# uart_usb_bridge.net
KiCad netlist of a schematic drawn in Altium Designer
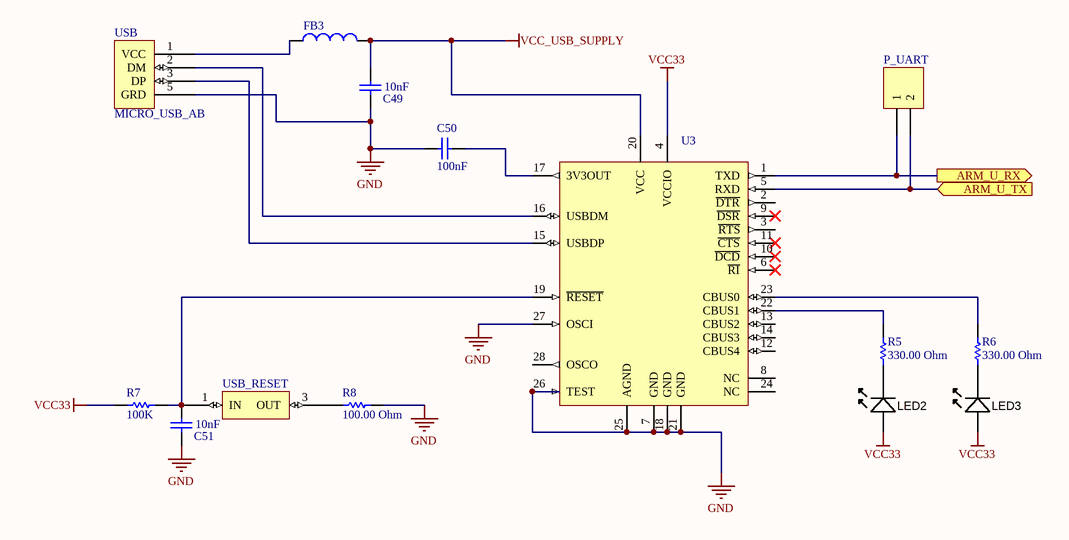
[diagram p0: uart_usb_bridge.SchDoc]

(export (version "E")
  (design (tool "Eeschema 10.0.6"))
  (components
    (comp (ref "C49")
      (value "10nF")
      (footprint "CAPC0805(2012)75_N")
      (description "CAP 10nF 50V ±10% 0805 (2012 Metric) Thickness 0.75mm SMD")
      (fields (field (name "TOLERANCE") "±10%"))
      (libsource (lib "Altium Content Vault") (part "CMP-1036-03842-1"))
    )
    (comp (ref "C50")
      (value "100nF")
      (footprint "CAPC0805(2012)100_M")
      (description "CAP 100nF 50V ±10% 0805 (2012 Metric) Thickness 1mm SMD")
      (fields (field (name "TOLERANCE") "±10%"))
      (libsource (lib "Altium Content Vault") (part "CMP-1036-04420-1"))
    )
    (comp (ref "C51")
      (value "10nF")
      (footprint "CAPC0805(2012)75_N")
      (description "CAP 10nF 50V ±10% 0805 (2012 Metric) Thickness 0.75mm SMD")
      (fields (field (name "TOLERANCE") "±10%"))
      (libsource (lib "Altium Content Vault") (part "CMP-1036-03842-1"))
    )
    (comp (ref "FB3")
      (value "Inductor")
      (footprint "INDC3216")
      (fields (field (name "PUBLISHER") "Altium Limited"))
      (libsource (lib "Miscellaneous Devices") (part "Inductor"))
    )
    (comp (ref "LED2")
      (value "Red")
      (footprint "LED-0805-A")
      (description "LED, 0805 SMD, Red")
      (libsource (lib "PBL - Light Sources") (part "LED_SMD_Red_0805"))
    )
    (comp (ref "LED3")
      (value "Red")
      (footprint "LED-0805-A")
      (description "LED, 0805 SMD, Red")
      (libsource (lib "PBL - Light Sources") (part "LED_SMD_Red_0805"))
    )
    (comp (ref "P_UART")
      (value "Header 2")
      (footprint "HDR1X2")
      (description "Header, 2-Pin")
      (fields (field (name "PUBLISHER") "Altium Limited"))
      (libsource (lib "Miscellaneous Connectors") (part "Header 2"))
    )
    (comp (ref "R5")
      (value "330.00 Ohm")
      (footprint "RESC0805(2012)_M")
      (description "330R 0.125W 1% 0805 (2012 Metric)  SMD")
      (fields (field (name "POWER") "0.125 W") (field (name "TOLERANCE") "1 %"))
      (libsource (lib "Altium Content Vault") (part "CMP-1013-00454-1"))
    )
    (comp (ref "R6")
      (value "330.00 Ohm")
      (footprint "RESC0805(2012)_M")
      (description "330R 0.125W 1% 0805 (2012 Metric)  SMD")
      (fields (field (name "POWER") "0.125 W") (field (name "TOLERANCE") "1 %"))
      (libsource (lib "Altium Content Vault") (part "CMP-1013-00454-1"))
    )
    (comp (ref "R7")
      (value "100K")
      (footprint "RESC0805(2012)_L")
      (description "100K 0.125W 5% 0805 (2012 Metric)  SMD")
      (fields (field (name "TOLERANCE") "5 %") (field (name "POWER") "0.125 W"))
      (libsource (lib "Altium Content Vault") (part "CMP-1013-00122-1"))
    )
    (comp (ref "R8")
      (value "100.00 Ohm")
      (footprint "RESC0805(2012)_M")
      (description "100R 0.125W 5% 0805 (2012 Metric)  SMD")
      (fields (field (name "TOLERANCE") "5 %") (field (name "POWER") "0.125 W"))
      (libsource (lib "Altium Content Vault") (part "CMP-1013-00050-1"))
    )
    (comp (ref "U3")
      (value "FT232RL-Reel")
      (footprint "SSOP-28_N")
      (description "USB UART Asynchronous Serial Data Transfer Chip, SSOP-28, Tape and Reel")
      (libsource (lib "FTDI Communication") (part "FT232RL-Reel"))
    )
    (comp (ref "USB")
      (value "MICRO_USB_AB")
      (footprint "MICRO_USB_AB")
      (libsource (lib "MICROUSB") (part "MICRO_USB_AB"))
    )
    (comp (ref "USB_RESET")
      (value "BUTTON")
      (footprint "BUTTON")
      (libsource (lib "PowerConnector") (part "BUTTON"))
    )
  )
  (nets
    (net (code "1") (name "/ARM_U_RX") (class "Default")
      (node (ref "P_UART") (pin "1") (pinfunction "1_1") (pintype "passive"))
      (node (ref "U3") (pin "1") (pinfunction "TXD_1") (pintype "output"))
    )
    (net (code "2") (name "/ARM_U_TX") (class "Default")
      (node (ref "P_UART") (pin "2") (pinfunction "2_2") (pintype "passive"))
      (node (ref "U3") (pin "5") (pinfunction "RXD_5") (pintype "input"))
    )
    (net (code "3") (name "GND") (class "Default")
      (node (ref "C49") (pin "1") (pinfunction "1_1") (pintype "passive"))
      (node (ref "C50") (pin "2") (pinfunction "2_2") (pintype "passive"))
      (node (ref "C51") (pin "1") (pinfunction "1_1") (pintype "passive"))
      (node (ref "R8") (pin "2") (pinfunction "2_2") (pintype "passive"))
      (node (ref "U3") (pin "18") (pinfunction "GND_18") (pintype "power_in"))
      (node (ref "U3") (pin "21") (pinfunction "GND_21") (pintype "power_in"))
      (node (ref "U3") (pin "25") (pinfunction "AGND_25") (pintype "power_in"))
      (node (ref "U3") (pin "26") (pinfunction "TEST_26") (pintype "input"))
      (node (ref "U3") (pin "27") (pinfunction "OSCI_27") (pintype "input"))
      (node (ref "U3") (pin "7") (pinfunction "GND_7") (pintype "power_in"))
      (node (ref "USB") (pin "5") (pinfunction "GRD_5") (pintype "power_in"))
    )
    (net (code "4") (name "Net-(LED2-PadK)") (class "Default")
      (node (ref "LED2") (pin "K") (pinfunction "K_K") (pintype "passive"))
      (node (ref "R5") (pin "1") (pinfunction "1_1") (pintype "passive"))
    )
    (net (code "5") (name "Net-(LED3-PadK)") (class "Default")
      (node (ref "LED3") (pin "K") (pinfunction "K_K") (pintype "passive"))
      (node (ref "R6") (pin "1") (pinfunction "1_1") (pintype "passive"))
    )
    (net (code "6") (name "Net-(U3-3V3OUT)") (class "Default")
      (node (ref "C50") (pin "1") (pinfunction "1_1") (pintype "passive"))
      (node (ref "U3") (pin "17") (pinfunction "3V3OUT_17") (pintype "output"))
    )
    (net (code "7") (name "Net-(U3-CBUS0)") (class "Default")
      (node (ref "R6") (pin "2") (pinfunction "2_2") (pintype "passive"))
      (node (ref "U3") (pin "23") (pinfunction "CBUS0_23") (pintype "bidirectional"))
    )
    (net (code "8") (name "Net-(U3-CBUS1)") (class "Default")
      (node (ref "R5") (pin "2") (pinfunction "2_2") (pintype "passive"))
      (node (ref "U3") (pin "22") (pinfunction "CBUS1_22") (pintype "bidirectional"))
    )
    (net (code "9") (name "Net-(U3-USBDM)") (class "Default")
      (node (ref "U3") (pin "16") (pinfunction "USBDM_16") (pintype "bidirectional"))
      (node (ref "USB") (pin "2") (pinfunction "DM_2") (pintype "bidirectional"))
    )
    (net (code "10") (name "Net-(U3-USBDP)") (class "Default")
      (node (ref "U3") (pin "15") (pinfunction "USBDP_15") (pintype "bidirectional"))
      (node (ref "USB") (pin "3") (pinfunction "DP_3") (pintype "bidirectional"))
    )
    (net (code "11") (name "Net-(U3-~{RESET})") (class "Default")
      (node (ref "C51") (pin "2") (pinfunction "2_2") (pintype "passive"))
      (node (ref "R7") (pin "1") (pinfunction "1_1") (pintype "passive"))
      (node (ref "U3") (pin "19") (pinfunction "~{RESET}_19") (pintype "input"))
      (node (ref "USB_RESET") (pin "1") (pinfunction "IN_1") (pintype "bidirectional"))
    )
    (net (code "12") (name "Net-(USB-VCC)") (class "Default")
      (node (ref "FB3") (pin "1") (pinfunction "1_1") (pintype "passive"))
      (node (ref "USB") (pin "1") (pinfunction "VCC_1") (pintype "power_in"))
    )
    (net (code "13") (name "Net-(USB_RESET-OUT)") (class "Default")
      (node (ref "R8") (pin "1") (pinfunction "1_1") (pintype "passive"))
      (node (ref "USB_RESET") (pin "3") (pinfunction "OUT_3") (pintype "bidirectional"))
    )
    (net (code "14") (name "VCC33") (class "Default")
      (node (ref "LED2") (pin "A") (pinfunction "A_A") (pintype "passive"))
      (node (ref "LED3") (pin "A") (pinfunction "A_A") (pintype "passive"))
      (node (ref "R7") (pin "2") (pinfunction "2_2") (pintype "passive"))
      (node (ref "U3") (pin "4") (pinfunction "VCCIO_4") (pintype "power_in"))
    )
    (net (code "15") (name "VCC_USB_SUPPLY") (class "Default")
      (node (ref "C49") (pin "2") (pinfunction "2_2") (pintype "passive"))
      (node (ref "FB3") (pin "2") (pinfunction "2_2") (pintype "passive"))
      (node (ref "U3") (pin "20") (pinfunction "VCC_20") (pintype "power_in"))
    )
    (net (code "16") (name "unconnected-(U3-CBUS2-Pad13)") (class "Default")
      (node (ref "U3") (pin "13") (pinfunction "CBUS2_13") (pintype "bidirectional"))
    )
    (net (code "17") (name "unconnected-(U3-CBUS3-Pad14)") (class "Default")
      (node (ref "U3") (pin "14") (pinfunction "CBUS3_14") (pintype "bidirectional"))
    )
    (net (code "18") (name "unconnected-(U3-CBUS4-Pad12)") (class "Default")
      (node (ref "U3") (pin "12") (pinfunction "CBUS4_12") (pintype "bidirectional"))
    )
    (net (code "19") (name "unconnected-(U3-NC-Pad8)") (class "Default")
      (node (ref "U3") (pin "8") (pinfunction "NC_8") (pintype "passive"))
    )
    (net (code "20") (name "unconnected-(U3-NC-Pad24)") (class "Default")
      (node (ref "U3") (pin "24") (pinfunction "NC_24") (pintype "passive"))
    )
    (net (code "21") (name "unconnected-(U3-OSCO-Pad28)") (class "Default")
      (node (ref "U3") (pin "28") (pinfunction "OSCO_28") (pintype "output"))
    )
    (net (code "22") (name "unconnected-(U3-~{CTS}-Pad11)") (class "Default")
      (node (ref "U3") (pin "11") (pinfunction "~{CTS}_11") (pintype "input+no_connect"))
    )
    (net (code "23") (name "unconnected-(U3-~{DCD}-Pad10)") (class "Default")
      (node (ref "U3") (pin "10") (pinfunction "~{DCD}_10") (pintype "input+no_connect"))
    )
    (net (code "24") (name "unconnected-(U3-~{DSR}-Pad9)") (class "Default")
      (node (ref "U3") (pin "9") (pinfunction "~{DSR}_9") (pintype "input+no_connect"))
    )
    (net (code "25") (name "unconnected-(U3-~{DTR}-Pad2)") (class "Default")
      (node (ref "U3") (pin "2") (pinfunction "~{DTR}_2") (pintype "output"))
    )
    (net (code "26") (name "unconnected-(U3-~{RI}-Pad6)") (class "Default")
      (node (ref "U3") (pin "6") (pinfunction "~{RI}_6") (pintype "input+no_connect"))
    )
    (net (code "27") (name "unconnected-(U3-~{RTS}-Pad3)") (class "Default")
      (node (ref "U3") (pin "3") (pinfunction "~{RTS}_3") (pintype "output"))
    )
  )
)
